# Encoder.net
KiCad netlist of a schematic drawn in Altium Designer
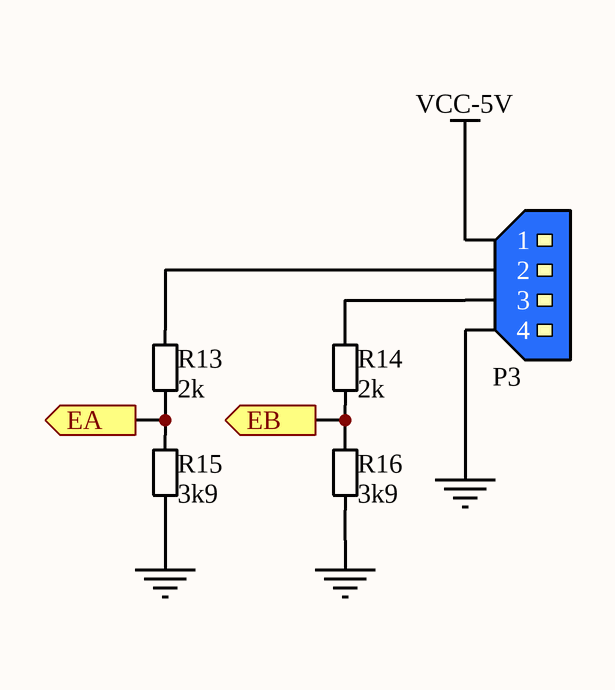
[diagram p0: Encoder.SchDoc]

(export (version "E")
  (design (tool "Eeschema 10.0.6"))
  (components
    (comp (ref "P3")
      (value "TE CONNECTIVITY_4PIN_MALE")
      (footprint "TE CONNECTIVITY_4PIN_MALE")
      (description "BLUE_4PIN_CONECTOR")
      (fields (field (name "MANUFACTURER") "TE CONNECTIVITY / AMP"))
      (libsource (lib "Electro_Mechanical") (part "TE CONNECTIVITY_4PIN_MALE"))
    )
    (comp (ref "R13")
      (value "2k")
      (footprint "RESC2013X38N-0805-NOOVERLAY")
      (description "RES SMD 2 kOhm 1/8W 0805")
      (fields (field (name "POWER") "0.125W, 1/8W"))
      (libsource (lib "Resistors") (part "00002001"))
    )
    (comp (ref "R14")
      (value "2k")
      (footprint "RESC2013X38N-0805-NOOVERLAY")
      (description "RES SMD 2 kOhm 1/8W 0805")
      (fields (field (name "POWER") "0.125W, 1/8W"))
      (libsource (lib "Resistors") (part "00002001"))
    )
    (comp (ref "R15")
      (value "3k9")
      (footprint "RESC2013X38N-0805-NOOVERLAY")
      (description "RES SMD 3.9 kOhm 1/8W 0805")
      (fields (field (name "POWER") "0.125W, 1/8W"))
      (libsource (lib "Resistors") (part "00003901"))
    )
    (comp (ref "R16")
      (value "3k9")
      (footprint "RESC2013X38N-0805-NOOVERLAY")
      (description "RES SMD 3.9 kOhm 1/8W 0805")
      (fields (field (name "POWER") "0.125W, 1/8W"))
      (libsource (lib "Resistors") (part "00003901"))
    )
  )
  (nets
    (net (code "1") (name "/EA") (class "Default")
      (node (ref "R13") (pin "1") (pinfunction "1_1") (pintype "passive"))
      (node (ref "R15") (pin "2") (pinfunction "2_2") (pintype "passive"))
    )
    (net (code "2") (name "/EB") (class "Default")
      (node (ref "R14") (pin "1") (pinfunction "1_1") (pintype "passive"))
      (node (ref "R16") (pin "2") (pinfunction "2_2") (pintype "passive"))
    )
    (net (code "3") (name "GND") (class "Default")
      (node (ref "P3") (pin "4") (pinfunction "4_4") (pintype "passive"))
      (node (ref "R15") (pin "1") (pinfunction "1_1") (pintype "passive"))
      (node (ref "R16") (pin "1") (pinfunction "1_1") (pintype "passive"))
    )
    (net (code "4") (name "Net-(P3-Pad2)") (class "Default")
      (node (ref "P3") (pin "2") (pinfunction "2_2") (pintype "passive"))
      (node (ref "R13") (pin "2") (pinfunction "2_2") (pintype "passive"))
    )
    (net (code "5") (name "Net-(P3-Pad3)") (class "Default")
      (node (ref "P3") (pin "3") (pinfunction "3_3") (pintype "passive"))
      (node (ref "R14") (pin "2") (pinfunction "2_2") (pintype "passive"))
    )
    (net (code "6") (name "VCC-5V") (class "Default")
      (node (ref "P3") (pin "1") (pinfunction "1_1") (pintype "passive"))
    )
  )
)
